# BottomPanel.net
KiCad netlist of a schematic drawn in Altium Designer
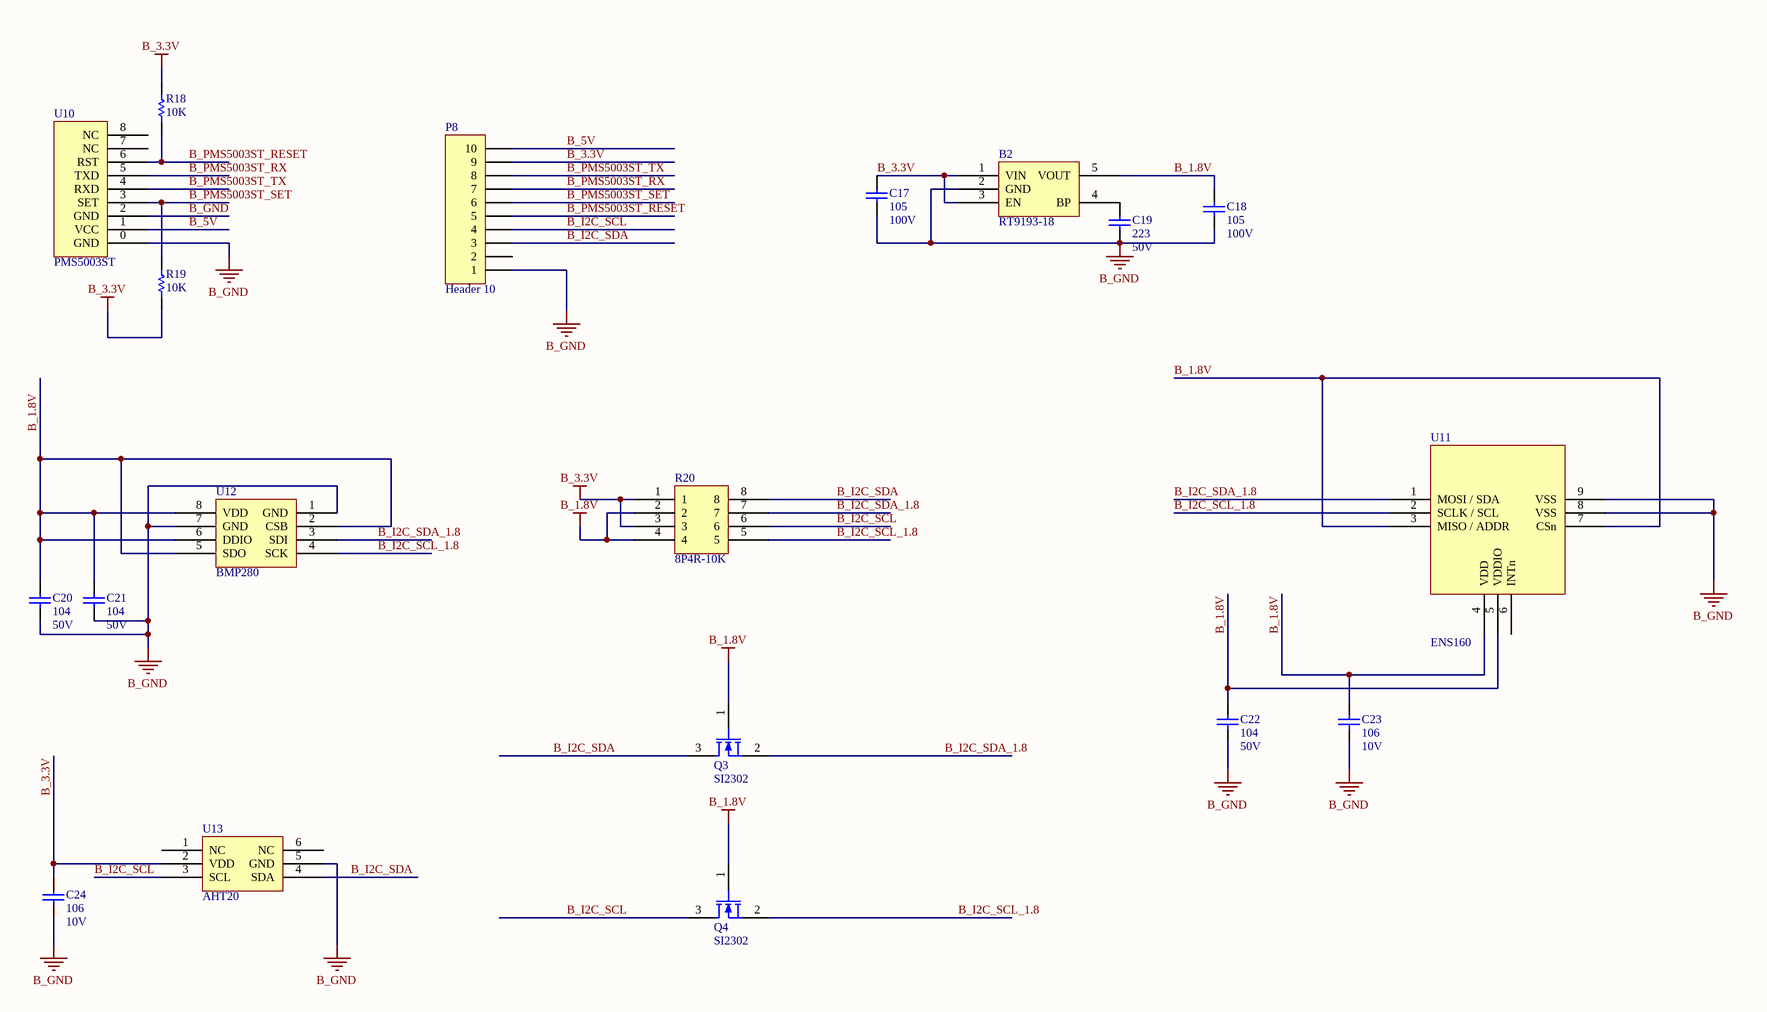
[diagram p0: BottomPanel.SchDoc]

(export (version "E")
  (design (tool "Eeschema 10.0.6"))
  (components
    (comp (ref "B2")
      (value "RT9193-18")
      (footprint "NeoIVClock:SOT23-5AL")
      (libsource (lib "NeoIVClock") (part "RT9193-18"))
    )
    (comp (ref "C17")
      (value "100V")
      (footprint "NeoIVClock:CAPC2012L")
      (description "Capacitor")
      (fields (field (name "ALTIUM_VALUE") "105") (field (name "PUBLISHER") "Altium Limited"))
      (libsource (lib "Miscellaneous Devices") (part "Cap"))
    )
    (comp (ref "C18")
      (value "100V")
      (footprint "NeoIVClock:CAPC2012L")
      (description "Capacitor")
      (fields (field (name "ALTIUM_VALUE") "105") (field (name "PUBLISHER") "Altium Limited"))
      (libsource (lib "Miscellaneous Devices") (part "Cap"))
    )
    (comp (ref "C19")
      (value "50V")
      (footprint "NeoIVClock:CAPC1608L")
      (description "Capacitor")
      (fields (field (name "ALTIUM_VALUE") "223") (field (name "PUBLISHER") "Altium Limited"))
      (libsource (lib "Miscellaneous Devices") (part "Cap"))
    )
    (comp (ref "C20")
      (value "50V")
      (footprint "NeoIVClock:CAPC1608L")
      (description "Capacitor")
      (fields (field (name "ALTIUM_VALUE") "104") (field (name "PUBLISHER") "Altium Limited"))
      (libsource (lib "Miscellaneous Devices") (part "Cap"))
    )
    (comp (ref "C21")
      (value "50V")
      (footprint "NeoIVClock:CAPC1608L")
      (description "Capacitor")
      (fields (field (name "ALTIUM_VALUE") "104") (field (name "PUBLISHER") "Altium Limited"))
      (libsource (lib "Miscellaneous Devices") (part "Cap"))
    )
    (comp (ref "C22")
      (value "50V")
      (footprint "NeoIVClock:CAPC1608L")
      (description "Capacitor")
      (fields (field (name "ALTIUM_VALUE") "104") (field (name "PUBLISHER") "Altium Limited"))
      (libsource (lib "Miscellaneous Devices") (part "Cap"))
    )
    (comp (ref "C23")
      (value "10V")
      (footprint "NeoIVClock:CAPC1608L")
      (description "Capacitor")
      (fields (field (name "ALTIUM_VALUE") "106") (field (name "PUBLISHER") "Altium Limited"))
      (libsource (lib "Miscellaneous Devices") (part "Cap"))
    )
    (comp (ref "C24")
      (value "10V")
      (footprint "NeoIVClock:CAPC1608L")
      (description "Capacitor")
      (fields (field (name "ALTIUM_VALUE") "106") (field (name "PUBLISHER") "Altium Limited"))
      (libsource (lib "Miscellaneous Devices") (part "Cap"))
    )
    (comp (ref "P8")
      (value "Header 10")
      (footprint "NeoIVClock:XH254-W-10P")
      (description "Header, 10-Pin")
      (fields (field (name "PUBLISHER") "Altium Limited"))
      (libsource (lib "Miscellaneous Connectors") (part "Header 10"))
    )
    (comp (ref "Q3")
      (value "SI2302")
      (footprint "NeoIVClock:SOT-23B_L")
      (description "N-Channel MOSFET")
      (fields (field (name "PUBLISHER") "Altium Limited"))
      (libsource (lib "Miscellaneous Devices") (part "MOSFET-N"))
    )
    (comp (ref "Q4")
      (value "SI2302")
      (footprint "NeoIVClock:SOT-23B_L")
      (description "N-Channel MOSFET")
      (fields (field (name "PUBLISHER") "Altium Limited"))
      (libsource (lib "Miscellaneous Devices") (part "MOSFET-N"))
    )
    (comp (ref "R18")
      (value "10K")
      (footprint "NeoIVClock:RESC1608L")
      (description "Resistor")
      (fields (field (name "Comment") "Res1") (field (name "PUBLISHER") "Altium Limited"))
      (libsource (lib "Miscellaneous Devices") (part "Res1"))
    )
    (comp (ref "R19")
      (value "10K")
      (footprint "NeoIVClock:RESC1608L")
      (description "Resistor")
      (fields (field (name "Comment") "Res1") (field (name "PUBLISHER") "Altium Limited"))
      (libsource (lib "Miscellaneous Devices") (part "Res1"))
    )
    (comp (ref "R20")
      (value "8P4R-10K")
      (footprint "NeoIVClock:8P4R 0603")
      (libsource (lib "NeoIVClock") (part "8P4R"))
    )
    (comp (ref "U10")
      (value "PMS5003ST")
      (footprint "NeoIVClock:PMS5003ST")
      (libsource (lib "NeoIVClock") (part "PMS5003ST"))
    )
    (comp (ref "U11")
      (value "ENS160")
      (footprint "NeoIVClock:ENS160")
      (libsource (lib "NeoIVClock") (part "ENS160"))
    )
    (comp (ref "U12") (value "BMP280") (footprint "BMP280") (libsource (lib "NeoIVClock") (part "BMP280")))
    (comp (ref "U13")
      (value "AHT20")
      (footprint "NeoIVClock:AHT20")
      (libsource (lib "NeoIVClock") (part "AHT20"))
    )
  )
  (nets
    (net (code "1") (name "/B_5V") (class "Default")
      (node (ref "P8") (pin "10") (pinfunction "10_10") (pintype "passive"))
      (node (ref "U10") (pin "1") (pinfunction "VCC_1") (pintype "passive"))
    )
    (net (code "2") (name "/B_I2C_SCL") (class "Default")
      (node (ref "P8") (pin "4") (pinfunction "4_4") (pintype "passive"))
      (node (ref "Q4") (pin "3") (pinfunction "D_3") (pintype "passive"))
      (node (ref "R20") (pin "6") (pinfunction "6_6") (pintype "passive"))
      (node (ref "U13") (pin "3") (pinfunction "SCL_3") (pintype "passive"))
    )
    (net (code "3") (name "/B_I2C_SCL_1.8") (class "Default")
      (node (ref "Q4") (pin "2") (pinfunction "S_2") (pintype "passive"))
      (node (ref "R20") (pin "5") (pinfunction "5_5") (pintype "passive"))
      (node (ref "U11") (pin "2") (pinfunction "SCLK_/_SCL_2") (pintype "passive"))
      (node (ref "U12") (pin "4") (pinfunction "SCK_4") (pintype "passive"))
    )
    (net (code "4") (name "/B_I2C_SDA") (class "Default")
      (node (ref "P8") (pin "3") (pinfunction "3_3") (pintype "passive"))
      (node (ref "Q3") (pin "3") (pinfunction "D_3") (pintype "passive"))
      (node (ref "R20") (pin "8") (pinfunction "8_8") (pintype "passive"))
      (node (ref "U13") (pin "4") (pinfunction "SDA_4") (pintype "passive"))
    )
    (net (code "5") (name "/B_I2C_SDA_1.8") (class "Default")
      (node (ref "Q3") (pin "2") (pinfunction "S_2") (pintype "passive"))
      (node (ref "R20") (pin "7") (pinfunction "7_7") (pintype "passive"))
      (node (ref "U11") (pin "1") (pinfunction "MOSI_/_SDA_1") (pintype "passive"))
      (node (ref "U12") (pin "3") (pinfunction "SDI_3") (pintype "passive"))
    )
    (net (code "6") (name "/B_PMS5003ST_RESET") (class "Default")
      (node (ref "P8") (pin "5") (pinfunction "5_5") (pintype "passive"))
      (node (ref "R18") (pin "2") (pinfunction "2_2") (pintype "passive"))
      (node (ref "U10") (pin "6") (pinfunction "RST_6") (pintype "passive"))
    )
    (net (code "7") (name "/B_PMS5003ST_RX") (class "Default")
      (node (ref "P8") (pin "7") (pinfunction "7_7") (pintype "passive"))
      (node (ref "U10") (pin "5") (pinfunction "TXD_5") (pintype "passive"))
    )
    (net (code "8") (name "/B_PMS5003ST_SET") (class "Default")
      (node (ref "P8") (pin "6") (pinfunction "6_6") (pintype "passive"))
      (node (ref "R19") (pin "1") (pinfunction "1_1") (pintype "passive"))
      (node (ref "U10") (pin "3") (pinfunction "SET_3") (pintype "passive"))
    )
    (net (code "9") (name "/B_PMS5003ST_TX") (class "Default")
      (node (ref "P8") (pin "8") (pinfunction "8_8") (pintype "passive"))
      (node (ref "U10") (pin "4") (pinfunction "RXD_4") (pintype "passive"))
    )
    (net (code "10") (name "B_1.8V") (class "Default")
      (node (ref "B2") (pin "5") (pinfunction "VOUT_5") (pintype "passive"))
      (node (ref "C18") (pin "2") (pinfunction "2_2") (pintype "passive"))
      (node (ref "C20") (pin "2") (pinfunction "2_2") (pintype "passive"))
      (node (ref "C21") (pin "2") (pinfunction "2_2") (pintype "passive"))
      (node (ref "C22") (pin "2") (pinfunction "2_2") (pintype "passive"))
      (node (ref "C23") (pin "2") (pinfunction "2_2") (pintype "passive"))
      (node (ref "Q3") (pin "1") (pinfunction "G_1") (pintype "passive"))
      (node (ref "Q4") (pin "1") (pinfunction "G_1") (pintype "passive"))
      (node (ref "R20") (pin "2") (pinfunction "2_2") (pintype "passive"))
      (node (ref "R20") (pin "4") (pinfunction "4_4") (pintype "passive"))
      (node (ref "U11") (pin "3") (pinfunction "MISO_/_ADDR_3") (pintype "passive"))
      (node (ref "U11") (pin "4") (pinfunction "VDD_4") (pintype "passive"))
      (node (ref "U11") (pin "5") (pinfunction "VDDIO_5") (pintype "passive"))
      (node (ref "U11") (pin "7") (pinfunction "CSn_7") (pintype "passive"))
      (node (ref "U12") (pin "2") (pinfunction "CSB_2") (pintype "passive"))
      (node (ref "U12") (pin "5") (pinfunction "SDO_5") (pintype "passive"))
      (node (ref "U12") (pin "6") (pinfunction "DDIO_6") (pintype "passive"))
      (node (ref "U12") (pin "8") (pinfunction "VDD_8") (pintype "passive"))
    )
    (net (code "11") (name "B_3.3V") (class "Default")
      (node (ref "B2") (pin "1") (pinfunction "VIN_1") (pintype "passive"))
      (node (ref "B2") (pin "3") (pinfunction "EN_3") (pintype "passive"))
      (node (ref "C17") (pin "2") (pinfunction "2_2") (pintype "passive"))
      (node (ref "C24") (pin "2") (pinfunction "2_2") (pintype "passive"))
      (node (ref "P8") (pin "9") (pinfunction "9_9") (pintype "passive"))
      (node (ref "R18") (pin "1") (pinfunction "1_1") (pintype "passive"))
      (node (ref "R19") (pin "2") (pinfunction "2_2") (pintype "passive"))
      (node (ref "R20") (pin "1") (pinfunction "1_1") (pintype "passive"))
      (node (ref "R20") (pin "3") (pinfunction "3_3") (pintype "passive"))
      (node (ref "U13") (pin "2") (pinfunction "VDD_2") (pintype "passive"))
    )
    (net (code "12") (name "B_GND") (class "Default")
      (node (ref "B2") (pin "2") (pinfunction "GND_2") (pintype "passive"))
      (node (ref "C17") (pin "1") (pinfunction "1_1") (pintype "passive"))
      (node (ref "C18") (pin "1") (pinfunction "1_1") (pintype "passive"))
      (node (ref "C19") (pin "1") (pinfunction "1_1") (pintype "passive"))
      (node (ref "C20") (pin "1") (pinfunction "1_1") (pintype "passive"))
      (node (ref "C21") (pin "1") (pinfunction "1_1") (pintype "passive"))
      (node (ref "C22") (pin "1") (pinfunction "1_1") (pintype "passive"))
      (node (ref "C23") (pin "1") (pinfunction "1_1") (pintype "passive"))
      (node (ref "C24") (pin "1") (pinfunction "1_1") (pintype "passive"))
      (node (ref "P8") (pin "1") (pinfunction "1_1") (pintype "passive"))
      (node (ref "U10") (pin "0") (pinfunction "GND_0") (pintype "passive"))
      (node (ref "U10") (pin "2") (pinfunction "GND_2") (pintype "passive"))
      (node (ref "U11") (pin "8") (pinfunction "VSS_8") (pintype "passive"))
      (node (ref "U11") (pin "9") (pinfunction "VSS_9") (pintype "passive"))
      (node (ref "U12") (pin "1") (pinfunction "GND_1") (pintype "passive"))
      (node (ref "U12") (pin "7") (pinfunction "GND_7") (pintype "passive"))
      (node (ref "U13") (pin "5") (pinfunction "GND_5") (pintype "passive"))
    )
    (net (code "13") (name "Net-(B2-BP)") (class "Default")
      (node (ref "B2") (pin "4") (pinfunction "BP_4") (pintype "passive"))
      (node (ref "C19") (pin "2") (pinfunction "2_2") (pintype "passive"))
    )
    (net (code "14") (name "unconnected-(P8-Pad2)") (class "Default")
      (node (ref "P8") (pin "2") (pinfunction "2_2") (pintype "passive"))
    )
    (net (code "15") (name "unconnected-(U10-NC-Pad7)") (class "Default")
      (node (ref "U10") (pin "7") (pinfunction "NC_7") (pintype "passive"))
    )
    (net (code "16") (name "unconnected-(U10-NC-Pad8)") (class "Default")
      (node (ref "U10") (pin "8") (pinfunction "NC_8") (pintype "passive"))
    )
    (net (code "17") (name "unconnected-(U11-INTn-Pad6)") (class "Default")
      (node (ref "U11") (pin "6") (pinfunction "INTn_6") (pintype "passive"))
    )
    (net (code "18") (name "unconnected-(U13-NC-Pad1)") (class "Default")
      (node (ref "U13") (pin "1") (pinfunction "NC_1") (pintype "passive"))
    )
    (net (code "19") (name "unconnected-(U13-NC-Pad6)") (class "Default")
      (node (ref "U13") (pin "6") (pinfunction "NC_6") (pintype "passive"))
    )
  )
)
